# V4-MySensors-LoRa-V004.net
KiCad netlist of a schematic drawn in EAGLE
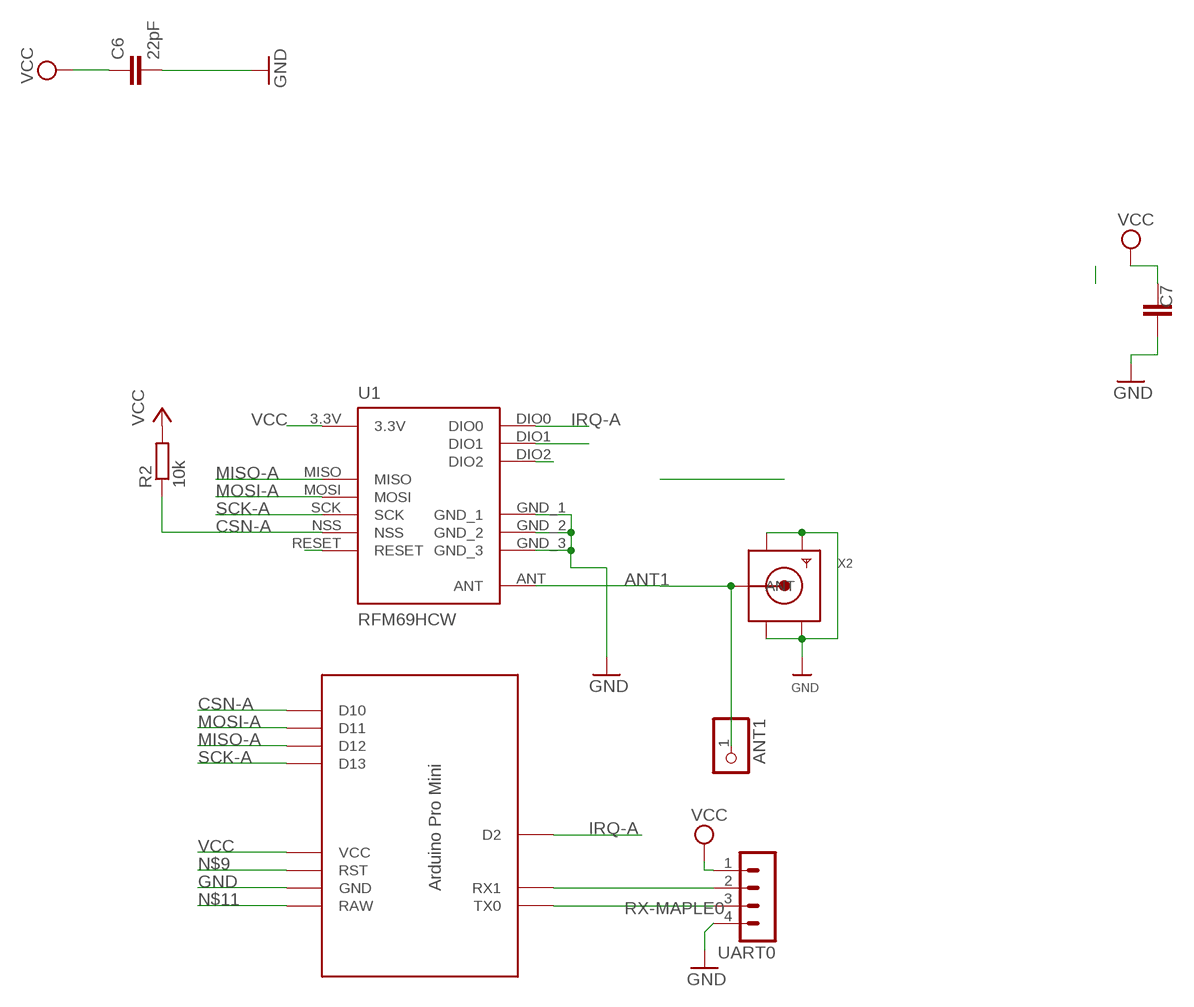
[diagram p0: schematic, sheet 1]

(export (version "E")
  (design (tool "Eeschema 10.0.6"))
  (components
    (comp (ref "ANT1")
      (value "PINHD-1X1")
      (footprint "eagle-import:1X01")
      (libsource (lib "eagle-import") (part "PINHD-1X1"))
    )
    (comp (ref "C6")
      (value "22pF")
      (footprint "eagle-import:C0805")
      (libsource (lib "eagle-import") (part "C-EUC0805"))
    )
    (comp (ref "C7")
      (value "C-EUC1812")
      (footprint "eagle-import:C1812")
      (libsource (lib "eagle-import") (part "C-EUC1812"))
    )
    (comp (ref "R2")
      (value "10k")
      (footprint "eagle-import:M0805")
      (libsource (lib "eagle-import") (part "R-EU_M0805"))
    )
    (comp (ref "U$1")
      (value "MARTIN-PROMINI-SPI")
      (footprint "eagle-import:MARTIN-PRO-SPI")
      (libsource (lib "eagle-import") (part "MARTIN-PROMINI-SPI"))
    )
    (comp (ref "U1")
      (value "RFM69HCW")
      (footprint "eagle-import:RFM69HCW-XXXS2")
      (libsource (lib "eagle-import") (part "RFM69HCW"))
    )
    (comp (ref "UART0")
      (value "MA04-1")
      (footprint "eagle-import:MA04-1")
      (libsource (lib "eagle-import") (part "MA04-1"))
    )
    (comp (ref "X2")
      (value "SMACONNECTOR_EDGE")
      (footprint "eagle-import:SMA_EDGELAUNCH")
      (libsource (lib "eagle-import") (part "SMACONNECTOR_EDGE"))
    )
  )
  (nets
    (net (code "1") (name "/ANT1") (class "Default")
      (node (ref "ANT1") (pin "1") (pinfunction "1_1") (pintype "passive"))
      (node (ref "U1") (pin "ANT") (pinfunction "ANT_ANT") (pintype "passive"))
      (node (ref "X2") (pin "P") (pinfunction "ANT_P") (pintype "bidirectional"))
    )
    (net (code "2") (name "/CSN-A") (class "Default")
      (node (ref "R2") (pin "1") (pinfunction "1_1") (pintype "passive"))
      (node (ref "U$1") (pin "D10") (pinfunction "D10_D10") (pintype "bidirectional"))
      (node (ref "U1") (pin "NSS") (pinfunction "NSS_NSS") (pintype "input"))
    )
    (net (code "3") (name "/IRQ-A") (class "Default")
      (node (ref "U$1") (pin "D2") (pinfunction "D2_D2") (pintype "bidirectional"))
      (node (ref "U1") (pin "DIO0") (pinfunction "DIO0_DIO0") (pintype "bidirectional"))
    )
    (net (code "4") (name "/MISO-A") (class "Default")
      (node (ref "U$1") (pin "D12") (pinfunction "D12_D12") (pintype "bidirectional"))
      (node (ref "U1") (pin "MISO") (pinfunction "MISO_MISO") (pintype "bidirectional"))
    )
    (net (code "5") (name "/MOSI-A") (class "Default")
      (node (ref "U$1") (pin "D11") (pinfunction "D11_D11") (pintype "bidirectional"))
      (node (ref "U1") (pin "MOSI") (pinfunction "MOSI_MOSI") (pintype "input"))
    )
    (net (code "6") (name "/N$9") (class "Default")
      (node (ref "U$1") (pin "RST") (pinfunction "RST_RST") (pintype "bidirectional"))
    )
    (net (code "7") (name "/N$11") (class "Default")
      (node (ref "U$1") (pin "RAW") (pinfunction "RAW_RAW") (pintype "bidirectional"))
    )
    (net (code "8") (name "/RX-MAPLE0") (class "Default")
      (node (ref "U$1") (pin "TX0") (pinfunction "TX0_TX0") (pintype "bidirectional"))
      (node (ref "UART0") (pin "3") (pinfunction "3_3") (pintype "passive"))
    )
    (net (code "9") (name "/SCK-A") (class "Default")
      (node (ref "U$1") (pin "D13") (pinfunction "D13_D13") (pintype "bidirectional"))
      (node (ref "U1") (pin "SCK") (pinfunction "SCK_SCK") (pintype "input"))
    )
    (net (code "10") (name "GND") (class "Default")
      (node (ref "C6") (pin "2") (pinfunction "2_2") (pintype "passive"))
      (node (ref "C7") (pin "1") (pinfunction "1_1") (pintype "passive"))
      (node (ref "U$1") (pin "GND") (pinfunction "GND_GND") (pintype "bidirectional"))
      (node (ref "U1") (pin "GND_1") (pinfunction "GND_1_GND_1") (pintype "power_in"))
      (node (ref "U1") (pin "GND_2") (pinfunction "GND_2_GND_2") (pintype "power_in"))
      (node (ref "U1") (pin "GND_3") (pinfunction "GND_3_GND_3") (pintype "power_in"))
      (node (ref "UART0") (pin "4") (pinfunction "4_4") (pintype "passive"))
      (node (ref "X2") (pin "GND@1") (pinfunction "GND4_GND@1") (pintype "power_in"))
      (node (ref "X2") (pin "GND@2") (pinfunction "GND3_GND@2") (pintype "power_in"))
      (node (ref "X2") (pin "GND@3") (pinfunction "GND2_GND@3") (pintype "power_in"))
      (node (ref "X2") (pin "GND@4") (pinfunction "GND1_GND@4") (pintype "power_in"))
    )
    (net (code "11") (name "Net-(U$1-PadRX1)") (class "Default")
      (node (ref "U$1") (pin "RX1") (pinfunction "RX1_RX1") (pintype "bidirectional"))
      (node (ref "UART0") (pin "2") (pinfunction "2_2") (pintype "passive"))
    )
    (net (code "12") (name "VCC") (class "Default")
      (node (ref "C6") (pin "1") (pinfunction "1_1") (pintype "passive"))
      (node (ref "C7") (pin "2") (pinfunction "2_2") (pintype "passive"))
      (node (ref "R2") (pin "2") (pinfunction "2_2") (pintype "passive"))
      (node (ref "U$1") (pin "VCC") (pinfunction "VCC_VCC") (pintype "bidirectional"))
      (node (ref "U1") (pin "3.3V") (pinfunction "3.3V_3.3V") (pintype "power_in"))
      (node (ref "UART0") (pin "1") (pinfunction "1_1") (pintype "passive"))
    )
    (net (code "13") (name "unconnected-(U1-PadDIO1)") (class "Default")
      (node (ref "U1") (pin "DIO1") (pinfunction "DIO1_DIO1") (pintype "bidirectional"))
    )
    (net (code "14") (name "unconnected-(U1-PadDIO2)") (class "Default")
      (node (ref "U1") (pin "DIO2") (pinfunction "DIO2_DIO2") (pintype "bidirectional"))
    )
    (net (code "15") (name "unconnected-(U1-PadRESET)") (class "Default")
      (node (ref "U1") (pin "RESET") (pinfunction "RESET_RESET") (pintype "input"))
    )
  )
)
